# t10_adapter_isp.net
KiCad netlist of a schematic drawn in EAGLE
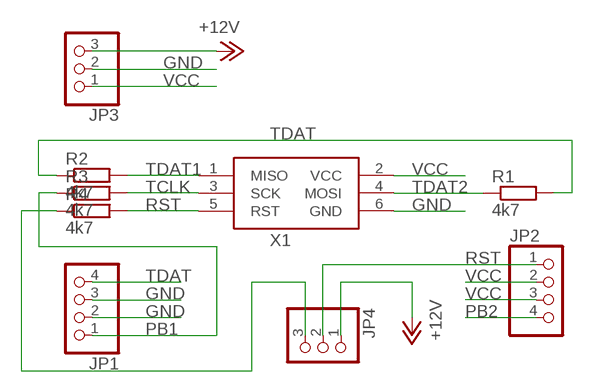
[diagram p0: schematic, sheet 1]

(export (version "E")
  (design (tool "Eeschema 10.0.6"))
  (components
    (comp (ref "JP1")
      (value "PINHD-1X4")
      (footprint "eagle-import:1X04")
      (libsource (lib "eagle-import") (part "PINHD-1X4"))
    )
    (comp (ref "JP2")
      (value "PINHD-1X4")
      (footprint "eagle-import:1X04")
      (libsource (lib "eagle-import") (part "PINHD-1X4"))
    )
    (comp (ref "JP3")
      (value "PINHD-1X3")
      (footprint "eagle-import:1X03")
      (libsource (lib "eagle-import") (part "PINHD-1X3"))
    )
    (comp (ref "JP4")
      (value "PINHD-1X3")
      (footprint "eagle-import:1X03")
      (libsource (lib "eagle-import") (part "PINHD-1X3"))
    )
    (comp (ref "R1")
      (value "4k7")
      (footprint "eagle-import:M0805")
      (libsource (lib "eagle-import") (part "R-EU_M0805"))
    )
    (comp (ref "R2")
      (value "4k7")
      (footprint "eagle-import:M0805")
      (libsource (lib "eagle-import") (part "R-EU_M0805"))
    )
    (comp (ref "R3")
      (value "4k7")
      (footprint "eagle-import:M0805")
      (libsource (lib "eagle-import") (part "R-EU_M0805"))
    )
    (comp (ref "R4")
      (value "4k7")
      (footprint "eagle-import:M0805")
      (libsource (lib "eagle-import") (part "R-EU_M0805"))
    )
    (comp (ref "X1")
      (value "AVRISP-HEADER-6-SHROUDED")
      (footprint "eagle-import:CONN-HARTING-ML6")
      (libsource (lib "eagle-import") (part "AVRISP-HEADER-6-SHROUDED"))
    )
  )
  (nets
    (net (code "1") (name "+12V") (class "Default")
      (node (ref "JP3") (pin "3") (pinfunction "3_3") (pintype "passive"))
      (node (ref "JP4") (pin "1") (pinfunction "1_1") (pintype "passive"))
    )
    (net (code "2") (name "/GND") (class "Default")
      (node (ref "JP1") (pin "2") (pinfunction "2_2") (pintype "passive"))
      (node (ref "JP1") (pin "3") (pinfunction "3_3") (pintype "passive"))
      (node (ref "JP3") (pin "2") (pinfunction "2_2") (pintype "passive"))
      (node (ref "X1") (pin "6") (pinfunction "GND_6") (pintype "power_in"))
    )
    (net (code "3") (name "/PB1") (class "Default")
      (node (ref "JP1") (pin "1") (pinfunction "1_1") (pintype "passive"))
      (node (ref "R3") (pin "1") (pinfunction "1_1") (pintype "passive"))
    )
    (net (code "4") (name "/PB2") (class "Default")
      (node (ref "JP2") (pin "4") (pinfunction "4_4") (pintype "passive"))
    )
    (net (code "5") (name "/RST") (class "Default")
      (node (ref "JP2") (pin "1") (pinfunction "1_1") (pintype "passive"))
      (node (ref "JP4") (pin "2") (pinfunction "2_2") (pintype "passive"))
      (node (ref "R4") (pin "2") (pinfunction "2_2") (pintype "passive"))
      (node (ref "X1") (pin "5") (pinfunction "RST_5") (pintype "output"))
    )
    (net (code "6") (name "/TCLK") (class "Default")
      (node (ref "R3") (pin "2") (pinfunction "2_2") (pintype "passive"))
      (node (ref "X1") (pin "3") (pinfunction "SCK_3") (pintype "output"))
    )
    (net (code "7") (name "/TDAT") (class "Default")
      (node (ref "JP1") (pin "4") (pinfunction "4_4") (pintype "passive"))
      (node (ref "R1") (pin "2") (pinfunction "2_2") (pintype "passive"))
      (node (ref "R2") (pin "1") (pinfunction "1_1") (pintype "passive"))
    )
    (net (code "8") (name "/TDAT1") (class "Default")
      (node (ref "R2") (pin "2") (pinfunction "2_2") (pintype "passive"))
      (node (ref "X1") (pin "1") (pinfunction "MISO_1") (pintype "input"))
    )
    (net (code "9") (name "/TDAT2") (class "Default")
      (node (ref "R1") (pin "1") (pinfunction "1_1") (pintype "passive"))
      (node (ref "X1") (pin "4") (pinfunction "MOSI_4") (pintype "output"))
    )
    (net (code "10") (name "/VCC") (class "Default")
      (node (ref "JP2") (pin "2") (pinfunction "2_2") (pintype "passive"))
      (node (ref "JP2") (pin "3") (pinfunction "3_3") (pintype "passive"))
      (node (ref "JP3") (pin "1") (pinfunction "1_1") (pintype "passive"))
      (node (ref "X1") (pin "2") (pinfunction "VCC_2") (pintype "power_in"))
    )
    (net (code "11") (name "Net-(JP4-Pad3)") (class "Default")
      (node (ref "JP4") (pin "3") (pinfunction "3_3") (pintype "passive"))
      (node (ref "R4") (pin "1") (pinfunction "1_1") (pintype "passive"))
    )
  )
)
